# 02_-_Power_Distribution.net
KiCad netlist of a schematic drawn in Altium Designer
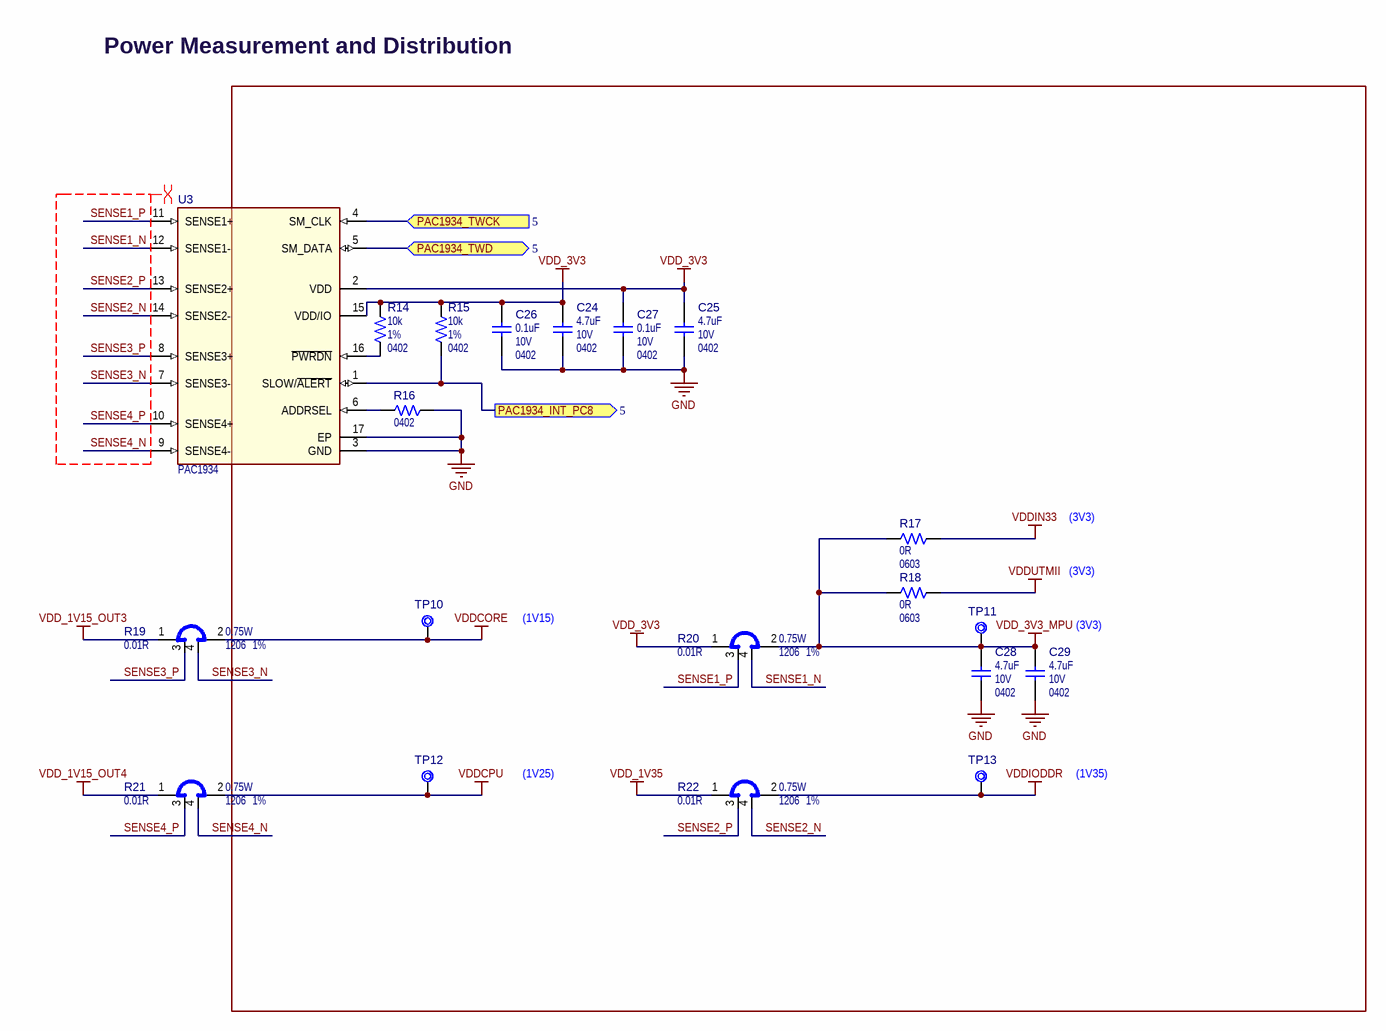
[diagram p0: 02 - Power Distribution.SchDoc]

(export (version "E")
  (design (tool "Eeschema 10.0.6"))
  (components
    (comp (ref "C24")
      (value "4.7uF")
      (footprint "CAP_C_0402")
      (description "Capacitor")
      (fields
        (field (name "VOLTAGE") "10V")
        (field (name "PACKAGE") "0402")
        (field (name "TOLERANCE") "10%")
        (field (name "Comment") "Capacitor NP")
        (field (name "OWNER") "Jesus Aviles")
      )
      (libsource (lib "MCHP-CDB") (part "Capacitor NP"))
    )
    (comp (ref "C25")
      (value "4.7uF")
      (footprint "CAP_C_0402")
      (description "Capacitor")
      (fields
        (field (name "VOLTAGE") "10V")
        (field (name "PACKAGE") "0402")
        (field (name "TOLERANCE") "10%")
        (field (name "Comment") "Capacitor NP")
        (field (name "OWNER") "Jesus Aviles")
      )
      (libsource (lib "MCHP-CDB") (part "Capacitor NP"))
    )
    (comp (ref "C26")
      (value "0.1uF")
      (footprint "CAP_C_0402")
      (description "Capacitor")
      (fields
        (field (name "VOLTAGE") "10V")
        (field (name "PACKAGE") "0402")
        (field (name "TOLERANCE") "10%")
        (field (name "Comment") "Capacitor NP")
        (field (name "OWNER") "Tad Ahlvers")
      )
      (libsource (lib "MCHP-CDB") (part "Capacitor NP"))
    )
    (comp (ref "C27")
      (value "0.1uF")
      (footprint "CAP_C_0402")
      (description "Capacitor")
      (fields
        (field (name "VOLTAGE") "10V")
        (field (name "PACKAGE") "0402")
        (field (name "TOLERANCE") "10%")
        (field (name "Comment") "Capacitor NP")
        (field (name "OWNER") "Tad Ahlvers")
      )
      (libsource (lib "MCHP-CDB") (part "Capacitor NP"))
    )
    (comp (ref "C28")
      (value "4.7uF")
      (footprint "CAP_C_0402")
      (description "Capacitor")
      (fields
        (field (name "VOLTAGE") "10V")
        (field (name "PACKAGE") "0402")
        (field (name "TOLERANCE") "10%")
        (field (name "Comment") "Capacitor NP")
        (field (name "OWNER") "Jesus Aviles")
      )
      (libsource (lib "MCHP-CDB") (part "Capacitor NP"))
    )
    (comp (ref "C29")
      (value "4.7uF")
      (footprint "CAP_C_0402")
      (description "Capacitor")
      (fields
        (field (name "VOLTAGE") "10V")
        (field (name "PACKAGE") "0402")
        (field (name "TOLERANCE") "10%")
        (field (name "Comment") "Capacitor NP")
        (field (name "OWNER") "Jesus Aviles")
      )
      (libsource (lib "MCHP-CDB") (part "Capacitor NP"))
    )
    (comp (ref "R14")
      (value "10k")
      (footprint "RES_C_0402")
      (description "Resistor")
      (fields
        (field (name "PACKAGE") "0402")
        (field (name "TOLERANCE") "1%")
        (field (name "VOLTAGE") "50V")
        (field (name "POWER") "1/10W")
        (field (name "OWNER") "Brent Lanphear")
      )
      (libsource (lib "MCHP-CDB") (part "Resistor"))
    )
    (comp (ref "R15")
      (value "10k")
      (footprint "RES_C_0402")
      (description "Resistor")
      (fields
        (field (name "PACKAGE") "0402")
        (field (name "TOLERANCE") "1%")
        (field (name "VOLTAGE") "50V")
        (field (name "POWER") "1/10W")
        (field (name "OWNER") "Brent Lanphear")
      )
      (libsource (lib "MCHP-CDB") (part "Resistor"))
    )
    (comp (ref "R16")
      (value "Resistor")
      (footprint "RES_C_0402")
      (fields
        (field (name "PACKAGE") "0402")
        (field (name "POWER") "1/16W")
        (field (name "VOLTAGE") "50V")
        (field (name "OWNER") "Dragos Danaila")
      )
      (libsource (lib "MCHP-CDB") (part "Resistor"))
    )
    (comp (ref "R17")
      (value "0R")
      (footprint "RES_C_0603")
      (description "Resistor")
      (fields (field (name "PACKAGE") "0603") (field (name "POWER") "1/10W"))
      (libsource (lib "MCHP-CDB") (part "Resistor"))
    )
    (comp (ref "R18")
      (value "0R")
      (footprint "RES_C_0603")
      (description "Resistor")
      (fields (field (name "PACKAGE") "0603") (field (name "POWER") "1/10W"))
      (libsource (lib "MCHP-CDB") (part "Resistor"))
    )
    (comp (ref "R19")
      (value "0.01R")
      (footprint "RES_C_1206_SHUNT")
      (description "Shunt")
      (fields
        (field (name "PACKAGE") "1206")
        (field (name "TOLERANCE") "1%")
        (field (name "POWER") "0.75W")
        (field (name "Comment") "Shunt 4 Pin")
        (field (name "OWNER") "Ciprian Abramov")
      )
      (libsource (lib "MCHP-CDB") (part "Shunt 4 Pin"))
    )
    (comp (ref "R20")
      (value "0.01R")
      (footprint "RES_C_1206_SHUNT")
      (description "Shunt")
      (fields
        (field (name "PACKAGE") "1206")
        (field (name "TOLERANCE") "1%")
        (field (name "POWER") "0.75W")
        (field (name "Comment") "Shunt 4 Pin")
        (field (name "OWNER") "Ciprian Abramov")
      )
      (libsource (lib "MCHP-CDB") (part "Shunt 4 Pin"))
    )
    (comp (ref "R21")
      (value "0.01R")
      (footprint "RES_C_1206_SHUNT")
      (description "Shunt")
      (fields
        (field (name "PACKAGE") "1206")
        (field (name "TOLERANCE") "1%")
        (field (name "POWER") "0.75W")
        (field (name "Comment") "Shunt 4 Pin")
        (field (name "OWNER") "Ciprian Abramov")
      )
      (libsource (lib "MCHP-CDB") (part "Shunt 4 Pin"))
    )
    (comp (ref "R22")
      (value "0.01R")
      (footprint "RES_C_1206_SHUNT")
      (description "Shunt")
      (fields
        (field (name "PACKAGE") "1206")
        (field (name "TOLERANCE") "1%")
        (field (name "POWER") "0.75W")
        (field (name "Comment") "Shunt 4 Pin")
        (field (name "OWNER") "Ciprian Abramov")
      )
      (libsource (lib "MCHP-CDB") (part "Shunt 4 Pin"))
    )
    (comp (ref "TP10")
      (value "Test Point No BOM")
      (footprint "TP_1mm_SMD")
      (description "Test Point")
      (fields (field (name "OWNER") "Cristian Papuc"))
      (libsource (lib "MCHP-CDB") (part "Test Point No BOM"))
    )
    (comp (ref "TP11")
      (value "Test Point No BOM")
      (footprint "TP_1mm_SMD")
      (description "Test Point")
      (fields (field (name "OWNER") "Cristian Papuc"))
      (libsource (lib "MCHP-CDB") (part "Test Point No BOM"))
    )
    (comp (ref "TP12")
      (value "Test Point No BOM")
      (footprint "TP_1mm_SMD")
      (description "Test Point")
      (fields (field (name "OWNER") "Cristian Papuc"))
      (libsource (lib "MCHP-CDB") (part "Test Point No BOM"))
    )
    (comp (ref "TP13")
      (value "Test Point No BOM")
      (footprint "TP_1mm_SMD")
      (description "Test Point")
      (fields (field (name "OWNER") "Cristian Papuc"))
      (libsource (lib "MCHP-CDB") (part "Test Point No BOM"))
    )
    (comp (ref "U3")
      (value "PAC1934")
      (footprint "UQFN-16_4X4_EP2.6X2.6")
      (fields (field (name "Comment") "PAC1934 UQFN-16") (field (name "OWNER") "Ciprian Abramov"))
      (libsource (lib "MCHP-CDB") (part "PAC1934 UQFN-16"))
    )
  )
  (nets
    (net (code "1") (name "/PAC1934_INT_PC8") (class "Default")
      (node (ref "R15") (pin "1") (pinfunction "1_1") (pintype "passive"))
      (node (ref "U3") (pin "1") (pinfunction "SLOW/~{ALERT}_1") (pintype "bidirectional"))
    )
    (net (code "2") (name "/PAC1934_TWCK") (class "Default")
      (node (ref "U3") (pin "4") (pinfunction "SM_CLK_4") (pintype "input"))
    )
    (net (code "3") (name "/PAC1934_TWD") (class "Default")
      (node (ref "U3") (pin "5") (pinfunction "SM_DATA_5") (pintype "bidirectional"))
    )
    (net (code "4") (name "/SENSE1_N") (class "Default")
      (node (ref "R20") (pin "4") (pinfunction "4_4") (pintype "passive"))
      (node (ref "U3") (pin "12") (pinfunction "SENSE1-_12") (pintype "input"))
    )
    (net (code "5") (name "/SENSE1_P") (class "Default")
      (node (ref "R20") (pin "3") (pinfunction "3_3") (pintype "passive"))
      (node (ref "U3") (pin "11") (pinfunction "SENSE1+_11") (pintype "input"))
    )
    (net (code "6") (name "/SENSE2_N") (class "Default")
      (node (ref "R22") (pin "4") (pinfunction "4_4") (pintype "passive"))
      (node (ref "U3") (pin "14") (pinfunction "SENSE2-_14") (pintype "input"))
    )
    (net (code "7") (name "/SENSE2_P") (class "Default")
      (node (ref "R22") (pin "3") (pinfunction "3_3") (pintype "passive"))
      (node (ref "U3") (pin "13") (pinfunction "SENSE2+_13") (pintype "input"))
    )
    (net (code "8") (name "/SENSE3_N") (class "Default")
      (node (ref "R19") (pin "4") (pinfunction "4_4") (pintype "passive"))
      (node (ref "U3") (pin "7") (pinfunction "SENSE3-_7") (pintype "input"))
    )
    (net (code "9") (name "/SENSE3_P") (class "Default")
      (node (ref "R19") (pin "3") (pinfunction "3_3") (pintype "passive"))
      (node (ref "U3") (pin "8") (pinfunction "SENSE3+_8") (pintype "input"))
    )
    (net (code "10") (name "/SENSE4_N") (class "Default")
      (node (ref "R21") (pin "4") (pinfunction "4_4") (pintype "passive"))
      (node (ref "U3") (pin "9") (pinfunction "SENSE4-_9") (pintype "input"))
    )
    (net (code "11") (name "/SENSE4_P") (class "Default")
      (node (ref "R21") (pin "3") (pinfunction "3_3") (pintype "passive"))
      (node (ref "U3") (pin "10") (pinfunction "SENSE4+_10") (pintype "input"))
    )
    (net (code "12") (name "GND") (class "Default")
      (node (ref "C24") (pin "1") (pinfunction "1_1") (pintype "passive"))
      (node (ref "C25") (pin "1") (pinfunction "1_1") (pintype "passive"))
      (node (ref "C26") (pin "1") (pinfunction "1_1") (pintype "passive"))
      (node (ref "C27") (pin "1") (pinfunction "1_1") (pintype "passive"))
      (node (ref "C28") (pin "1") (pinfunction "1_1") (pintype "passive"))
      (node (ref "C29") (pin "1") (pinfunction "1_1") (pintype "passive"))
      (node (ref "R16") (pin "2") (pinfunction "2_2") (pintype "passive"))
      (node (ref "U3") (pin "17") (pinfunction "EP_17") (pintype "passive"))
      (node (ref "U3") (pin "3") (pinfunction "GND_3") (pintype "power_in"))
    )
    (net (code "13") (name "Net-(U3-ADDRSEL)") (class "Default")
      (node (ref "R16") (pin "1") (pinfunction "1_1") (pintype "passive"))
      (node (ref "U3") (pin "6") (pinfunction "ADDRSEL_6") (pintype "input"))
    )
    (net (code "14") (name "Net-(U3-~{PWRDN})") (class "Default")
      (node (ref "R14") (pin "1") (pinfunction "1_1") (pintype "passive"))
      (node (ref "U3") (pin "16") (pinfunction "~{PWRDN}_16") (pintype "input"))
    )
    (net (code "15") (name "VDDCORE") (class "Default")
      (node (ref "R19") (pin "2") (pinfunction "2_2") (pintype "passive"))
      (node (ref "TP10") (pin "1") (pinfunction "1_1") (pintype "passive"))
    )
    (net (code "16") (name "VDDCPU") (class "Default")
      (node (ref "R21") (pin "2") (pinfunction "2_2") (pintype "passive"))
      (node (ref "TP12") (pin "1") (pinfunction "1_1") (pintype "passive"))
    )
    (net (code "17") (name "VDDIN33") (class "Default")
      (node (ref "R17") (pin "2") (pinfunction "2_2") (pintype "passive"))
    )
    (net (code "18") (name "VDDIODDR") (class "Default")
      (node (ref "R22") (pin "2") (pinfunction "2_2") (pintype "passive"))
      (node (ref "TP13") (pin "1") (pinfunction "1_1") (pintype "passive"))
    )
    (net (code "19") (name "VDDUTMII") (class "Default")
      (node (ref "R18") (pin "2") (pinfunction "2_2") (pintype "passive"))
    )
    (net (code "20") (name "VDD_1V15_OUT3") (class "Default")
      (node (ref "R19") (pin "1") (pinfunction "1_1") (pintype "passive"))
    )
    (net (code "21") (name "VDD_1V15_OUT4") (class "Default")
      (node (ref "R21") (pin "1") (pinfunction "1_1") (pintype "passive"))
    )
    (net (code "22") (name "VDD_1V35") (class "Default")
      (node (ref "R22") (pin "1") (pinfunction "1_1") (pintype "passive"))
    )
    (net (code "23") (name "VDD_3V3") (class "Default")
      (node (ref "C24") (pin "2") (pinfunction "2_2") (pintype "passive"))
      (node (ref "C25") (pin "2") (pinfunction "2_2") (pintype "passive"))
      (node (ref "C26") (pin "2") (pinfunction "2_2") (pintype "passive"))
      (node (ref "C27") (pin "2") (pinfunction "2_2") (pintype "passive"))
      (node (ref "R14") (pin "2") (pinfunction "2_2") (pintype "passive"))
      (node (ref "R15") (pin "2") (pinfunction "2_2") (pintype "passive"))
      (node (ref "R20") (pin "1") (pinfunction "1_1") (pintype "passive"))
      (node (ref "U3") (pin "15") (pinfunction "VDD/IO_15") (pintype "power_in"))
      (node (ref "U3") (pin "2") (pinfunction "VDD_2") (pintype "power_in"))
    )
    (net (code "24") (name "VDD_3V3_MPU") (class "Default")
      (node (ref "C28") (pin "2") (pinfunction "2_2") (pintype "passive"))
      (node (ref "C29") (pin "2") (pinfunction "2_2") (pintype "passive"))
      (node (ref "R17") (pin "1") (pinfunction "1_1") (pintype "passive"))
      (node (ref "R18") (pin "1") (pinfunction "1_1") (pintype "passive"))
      (node (ref "R20") (pin "2") (pinfunction "2_2") (pintype "passive"))
      (node (ref "TP11") (pin "1") (pinfunction "1_1") (pintype "passive"))
    )
  )
)
